# BUCK.net
KiCad netlist of a schematic drawn in Altium Designer
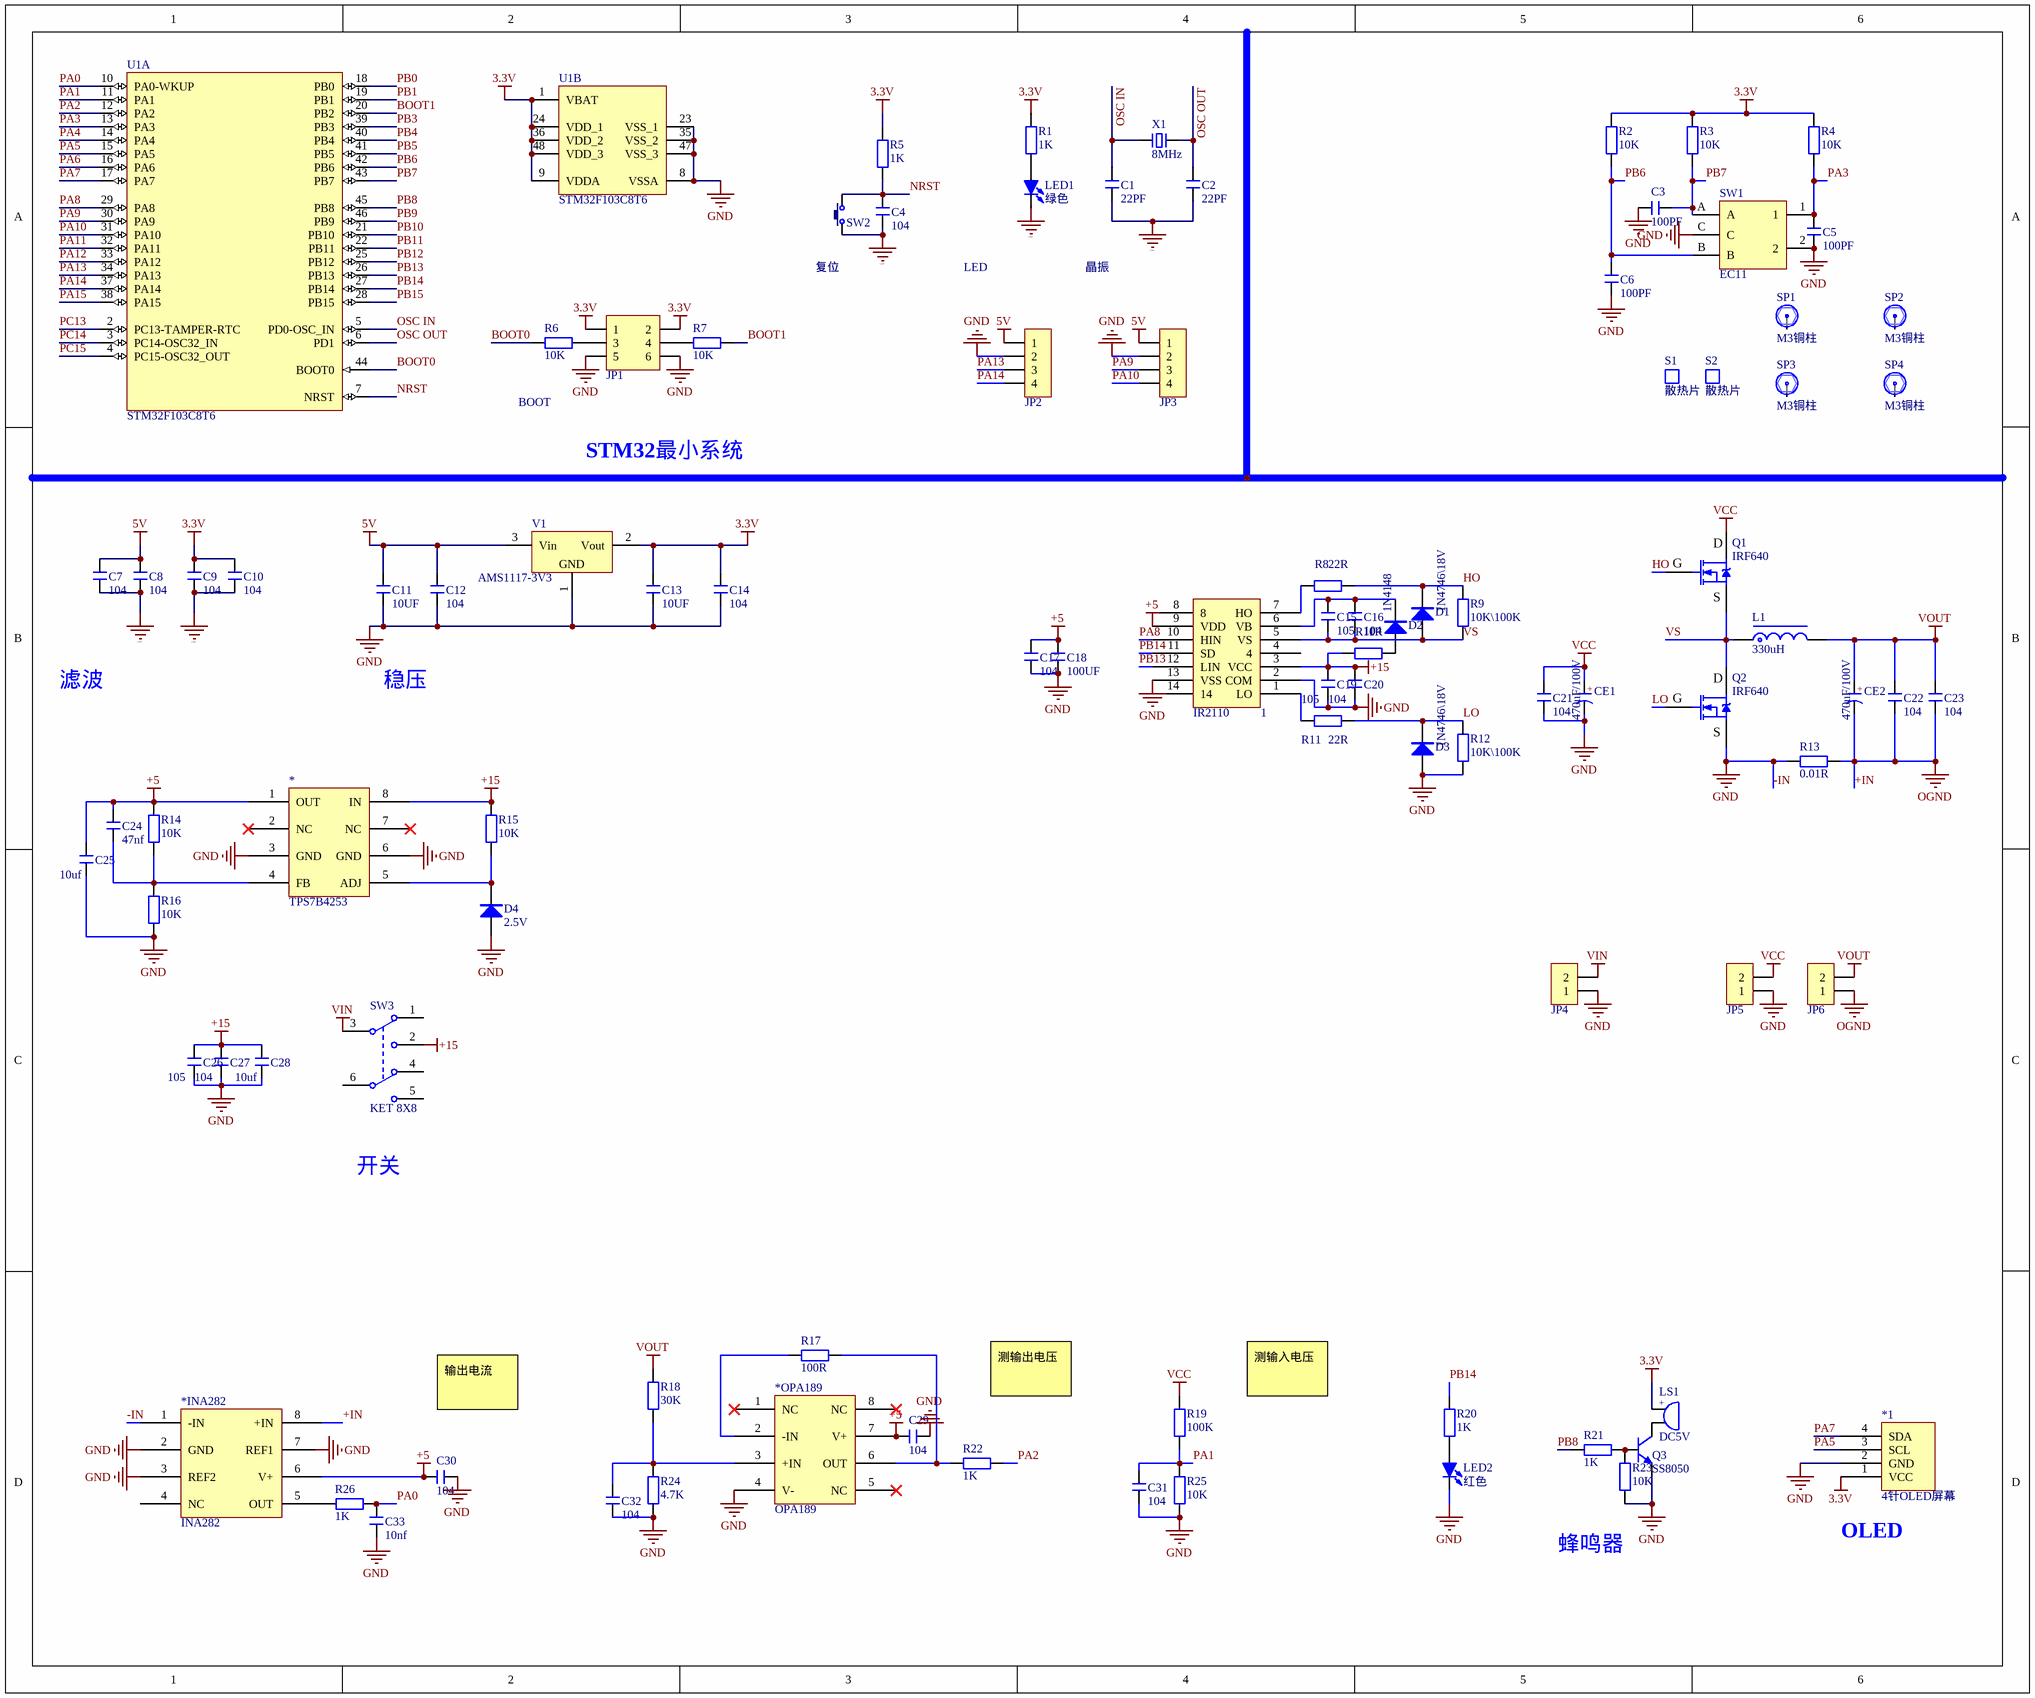
[diagram p0: BUCK开关电源.SchDoc]

(export (version "E")
  (design (tool "Eeschema 10.0.6"))
  (components
    (comp (ref "*")
      (value "TPS7B4253")
      (footprint "SOP8_M")
      (libsource (lib "1.1 - 电源类芯片") (part "TPS7B4253"))
    )
    (comp (ref "*1") (value "4针OLED屏幕") (footprint "4针OLED屏幕") (libsource (lib "4针OLED屏幕") (part "4针OLED屏幕")))
    (comp (ref "*INA282")
      (value "INA282")
      (footprint "SOP8_M")
      (libsource (lib "1.0 - 常见芯片") (part "INA282"))
    )
    (comp (ref "*OPA189")
      (value "OPA189")
      (footprint "SOP8_M")
      (libsource (lib "1.0 - 常见芯片") (part "OPA189"))
    )
    (comp (ref "1")
      (value "IR2110")
      (footprint "DIP14-300_MH")
      (libsource (lib "IR2110") (part "Component_1"))
    )
    (comp (ref "C1")
      (value "22PF")
      (footprint "C 0805_L")
      (description "贴片电容")
      (libsource (lib "0.1 - 电阻-电容-电感") (part "C"))
    )
    (comp (ref "C2")
      (value "22PF")
      (footprint "C 0805_L")
      (description "贴片电容")
      (libsource (lib "0.1 - 电阻-电容-电感") (part "C"))
    )
    (comp (ref "C3")
      (value "100PF")
      (footprint "C 0805_L")
      (description "贴片电容")
      (libsource (lib "0.1 - 电阻-电容-电感") (part "C"))
    )
    (comp (ref "C4")
      (value "104")
      (footprint "C 0805_L")
      (description "贴片电容")
      (libsource (lib "0.1 - 电阻-电容-电感") (part "C"))
    )
    (comp (ref "C5")
      (value "100PF")
      (footprint "C 0805_L")
      (description "贴片电容")
      (libsource (lib "0.1 - 电阻-电容-电感") (part "C"))
    )
    (comp (ref "C6")
      (value "100PF")
      (footprint "C 0805_L")
      (description "贴片电容")
      (libsource (lib "0.1 - 电阻-电容-电感") (part "C"))
    )
    (comp (ref "C7")
      (value "104")
      (footprint "C 0805_L")
      (description "贴片电容")
      (libsource (lib "0.1 - 电阻-电容-电感") (part "C"))
    )
    (comp (ref "C8")
      (value "104")
      (footprint "C 0805_L")
      (description "贴片电容")
      (libsource (lib "0.1 - 电阻-电容-电感") (part "C"))
    )
    (comp (ref "C9")
      (value "104")
      (footprint "C 0805_L")
      (description "贴片电容")
      (libsource (lib "0.1 - 电阻-电容-电感") (part "C"))
    )
    (comp (ref "C10")
      (value "104")
      (footprint "C 0805_L")
      (description "贴片电容")
      (libsource (lib "0.1 - 电阻-电容-电感") (part "C"))
    )
    (comp (ref "C11")
      (value "10UF")
      (footprint "C 0805_L")
      (description "贴片电容")
      (libsource (lib "0.1 - 电阻-电容-电感") (part "C"))
    )
    (comp (ref "C12")
      (value "104")
      (footprint "C 0805_L")
      (description "贴片电容")
      (libsource (lib "0.1 - 电阻-电容-电感") (part "C"))
    )
    (comp (ref "C13")
      (value "10UF")
      (footprint "C 0805_L")
      (description "贴片电容")
      (libsource (lib "0.1 - 电阻-电容-电感") (part "C"))
    )
    (comp (ref "C14")
      (value "104")
      (footprint "C 0805_L")
      (description "贴片电容")
      (libsource (lib "0.1 - 电阻-电容-电感") (part "C"))
    )
    (comp (ref "C15")
      (value "105")
      (footprint "C 0805_L")
      (description "贴片电容")
      (libsource (lib "0.1 - 电阻-电容-电感") (part "C"))
    )
    (comp (ref "C16")
      (value "104")
      (footprint "C 0805_L")
      (description "贴片电容")
      (libsource (lib "0.1 - 电阻-电容-电感") (part "C"))
    )
    (comp (ref "C17")
      (value "104")
      (footprint "C 0805_L")
      (description "贴片电容")
      (libsource (lib "0.1 - 电阻-电容-电感") (part "C"))
    )
    (comp (ref "C18")
      (value "100UF")
      (footprint "C 0805_L")
      (description "贴片电容")
      (libsource (lib "0.1 - 电阻-电容-电感") (part "C"))
    )
    (comp (ref "C19")
      (value "105")
      (footprint "C 0805_L")
      (description "贴片电容")
      (libsource (lib "0.1 - 电阻-电容-电感") (part "C"))
    )
    (comp (ref "C20")
      (value "104")
      (footprint "C 0805_L")
      (description "贴片电容")
      (libsource (lib "0.1 - 电阻-电容-电感") (part "C"))
    )
    (comp (ref "C21")
      (value "104")
      (footprint "C 0805_L")
      (description "贴片电容")
      (libsource (lib "0.1 - 电阻-电容-电感") (part "C"))
    )
    (comp (ref "C22")
      (value "104")
      (footprint "C 0805_L")
      (description "贴片电容")
      (libsource (lib "0.1 - 电阻-电容-电感") (part "C"))
    )
    (comp (ref "C23")
      (value "104")
      (footprint "C 0805_L")
      (description "贴片电容")
      (libsource (lib "0.1 - 电阻-电容-电感") (part "C"))
    )
    (comp (ref "C24")
      (value "47nf")
      (footprint "C 0805_L")
      (description "贴片电容")
      (libsource (lib "0.1 - 电阻-电容-电感") (part "C"))
    )
    (comp (ref "C25")
      (value "10uf")
      (footprint "C 0805_L")
      (description "贴片电容")
      (libsource (lib "0.1 - 电阻-电容-电感") (part "C"))
    )
    (comp (ref "C26")
      (value "105")
      (footprint "C 0805_L")
      (description "贴片电容")
      (libsource (lib "0.1 - 电阻-电容-电感") (part "C"))
    )
    (comp (ref "C27")
      (value "104")
      (footprint "C 0805_L")
      (description "贴片电容")
      (libsource (lib "0.1 - 电阻-电容-电感") (part "C"))
    )
    (comp (ref "C28")
      (value "10uf")
      (footprint "C 0805_L")
      (description "贴片电容")
      (libsource (lib "0.1 - 电阻-电容-电感") (part "C"))
    )
    (comp (ref "C29")
      (value "104")
      (footprint "C 0805_L")
      (description "贴片电容")
      (libsource (lib "0.1 - 电阻-电容-电感") (part "C"))
    )
    (comp (ref "C30")
      (value "104")
      (footprint "C 0805_L")
      (description "贴片电容")
      (libsource (lib "0.1 - 电阻-电容-电感") (part "C"))
    )
    (comp (ref "C31")
      (value "104")
      (footprint "C 0805_L")
      (description "贴片电容")
      (libsource (lib "0.1 - 电阻-电容-电感") (part "C"))
    )
    (comp (ref "C32")
      (value "104")
      (footprint "C 0805_L")
      (description "贴片电容")
      (libsource (lib "0.1 - 电阻-电容-电感") (part "C"))
    )
    (comp (ref "C33")
      (value "10nf")
      (footprint "C 0805_L")
      (description "贴片电容")
      (libsource (lib "0.1 - 电阻-电容-电感") (part "C"))
    )
    (comp (ref "CE1")
      (value "470uF/100V")
      (footprint "CAP 7.5*16*25 - BK")
      (description "直插电解电容")
      (libsource (lib "0.1 - 电阻-电容-电感") (part "CE"))
    )
    (comp (ref "CE2")
      (value "470uF/100V")
      (footprint "CAP 7.5*16*25 - BK")
      (description "直插电解电容")
      (libsource (lib "0.1 - 电阻-电容-电感") (part "CE"))
    )
    (comp (ref "D1")
      (value "1N474~{6}18V")
      (footprint "DO-35")
      (description "开关二极管")
      (libsource (lib "0.2 - 二极管-整流桥") (part "1N4148"))
    )
    (comp (ref "D2")
      (value "1N4148")
      (footprint "DO-35")
      (description "开关二极管")
      (libsource (lib "0.2 - 二极管-整流桥") (part "1N4148"))
    )
    (comp (ref "D3")
      (value "1N474~{6}18V")
      (footprint "DO-35")
      (description "开关二极管")
      (libsource (lib "0.2 - 二极管-整流桥") (part "1N4148"))
    )
    (comp (ref "D4")
      (value "2.5V")
      (footprint "DO-35")
      (description "开关二极管")
      (libsource (lib "0.2 - 二极管-整流桥") (part "1N4148"))
    )
    (comp (ref "JP1")
      (value "Header3X2")
      (footprint "HDR2.54-LI-2x3P")
      (description "3*2P接插件")
      (fields (field (name "版权归属") "封装库来自淘宝 ID：黄晶宝石"))
      (libsource (lib "5.4 - 接插件-脚距2.54 (100mil) ") (part "Header 3X2"))
    )
    (comp (ref "JP2")
      (value "HDR-1X4")
      (footprint "HDR2.54-WI-4P")
      (description "4P接插件")
      (fields (field (name "版权归属") "封装库来自淘宝 ID：黄晶宝石"))
      (libsource (lib "5.4 - 接插件-脚距2.54 (100mil) ") (part "Header 4"))
    )
    (comp (ref "JP3")
      (value "HDR-1X4")
      (footprint "HDR2.54-LI-4P")
      (description "4P接插件")
      (fields (field (name "版权归属") "封装库来自淘宝 ID：黄晶宝石"))
      (libsource (lib "5.4 - 接插件-脚距2.54 (100mil) ") (part "Header 4"))
    )
    (comp (ref "JP4")
      (value "HDR-1X2")
      (footprint "KF128-5.08-2P")
      (description "2P接插件")
      (fields (field (name "版权归属") "封装库来自淘宝卖家 ID：黄晶宝石"))
      (libsource (lib "6.1 - 接插件-脚距5.08 (200mil) ") (part "Header 2"))
    )
    (comp (ref "JP5")
      (value "HDR-1X2")
      (footprint "KF128-5.08-2P")
      (description "2P接插件")
      (fields (field (name "版权归属") "封装库来自淘宝卖家 ID：黄晶宝石"))
      (libsource (lib "6.1 - 接插件-脚距5.08 (200mil) ") (part "Header 2"))
    )
    (comp (ref "JP6")
      (value "HDR-1X2")
      (footprint "KF128-5.08-2P")
      (description "2P接插件")
      (fields (field (name "版权归属") "封装库来自淘宝卖家 ID：黄晶宝石"))
      (libsource (lib "6.1 - 接插件-脚距5.08 (200mil) ") (part "Header 2"))
    )
    (comp (ref "L1")
      (value "330uH")
      (footprint "直插磁环电感（大）")
      (description "功率磁环电感")
      (libsource (lib "0.1 - 电阻-电容-电感") (part "L-MR"))
    )
    (comp (ref "LED1")
      (value "绿色")
      (footprint "LED 0805W")
      (description "贴片LED")
      (fields (field (name "版权归属") "封装库来自淘宝 ID：黄晶宝石"))
      (libsource (lib "0.3 - LED发光二极管") (part "LED-SMD"))
    )
    (comp (ref "LED2")
      (value "红色")
      (footprint "LED 0603B")
      (description "贴片LED")
      (fields (field (name "版权归属") "封装库来自淘宝 ID：黄晶宝石"))
      (libsource (lib "0.3 - LED发光二极管") (part "LED-SMD"))
    )
    (comp (ref "LS1")
      (value "DC5V")
      (footprint "BEEP 7.6X12X7.5")
      (description "蜂鸣器")
      (fields (field (name "版权归属") "封装库来自淘宝 ID：黄晶宝石"))
      (libsource (lib "4.1 - 未分类器件") (part "BEEP"))
    )
    (comp (ref "Q1")
      (value "IRF640")
      (footprint "TO220A")
      (description "N沟场效应管")
      (libsource (lib "0.5 - 场效应管-可控硅") (part "IRF840"))
    )
    (comp (ref "Q2")
      (value "IRF640")
      (footprint "TO220A")
      (description "N沟场效应管")
      (libsource (lib "0.5 - 场效应管-可控硅") (part "IRF840"))
    )
    (comp (ref "Q3")
      (value "SS8050")
      (footprint "TO92A")
      (description "高频放大-NPN型")
      (fields (field (name "版权归属") "封装库来自淘宝 ID：黄晶宝石"))
      (libsource (lib "0.4 - 三极管") (part "8050-DIP"))
    )
    (comp (ref "R1")
      (value "1K")
      (footprint "R 0805_L")
      (description "贴片电阻")
      (fields (field (name "版权归属") "来自淘宝 ID：黄晶宝石"))
      (libsource (lib "0.1 - 电阻-电容-电感") (part "R"))
    )
    (comp (ref "R2")
      (value "10K")
      (footprint "R 0805_L")
      (description "贴片电阻")
      (fields (field (name "版权归属") "来自淘宝 ID：黄晶宝石"))
      (libsource (lib "0.1 - 电阻-电容-电感") (part "R"))
    )
    (comp (ref "R3")
      (value "10K")
      (footprint "R 0805_L")
      (description "贴片电阻")
      (fields (field (name "版权归属") "来自淘宝 ID：黄晶宝石"))
      (libsource (lib "0.1 - 电阻-电容-电感") (part "R"))
    )
    (comp (ref "R4")
      (value "10K")
      (footprint "R 0805_L")
      (description "贴片电阻")
      (fields (field (name "版权归属") "来自淘宝 ID：黄晶宝石"))
      (libsource (lib "0.1 - 电阻-电容-电感") (part "R"))
    )
    (comp (ref "R5")
      (value "1K")
      (footprint "R 0805_L")
      (description "贴片电阻")
      (fields (field (name "版权归属") "来自淘宝 ID：黄晶宝石"))
      (libsource (lib "0.1 - 电阻-电容-电感") (part "R"))
    )
    (comp (ref "R6")
      (value "10K")
      (footprint "R 0805_L")
      (description "贴片电阻")
      (fields (field (name "版权归属") "来自淘宝 ID：黄晶宝石"))
      (libsource (lib "0.1 - 电阻-电容-电感") (part "R"))
    )
    (comp (ref "R7")
      (value "10K")
      (footprint "R 0805_L")
      (description "贴片电阻")
      (fields (field (name "版权归属") "来自淘宝 ID：黄晶宝石"))
      (libsource (lib "0.1 - 电阻-电容-电感") (part "R"))
    )
    (comp (ref "R8")
      (value "22R")
      (footprint "R 0805_L")
      (description "贴片电阻")
      (fields (field (name "版权归属") "来自淘宝 ID：黄晶宝石"))
      (libsource (lib "0.1 - 电阻-电容-电感") (part "R"))
    )
    (comp (ref "R9")
      (value "10~{K}100K")
      (footprint "R 0805_L")
      (description "贴片电阻")
      (fields (field (name "版权归属") "来自淘宝 ID：黄晶宝石"))
      (libsource (lib "0.1 - 电阻-电容-电感") (part "R"))
    )
    (comp (ref "R10")
      (value "1R")
      (footprint "R 0805_L")
      (description "贴片电阻")
      (fields (field (name "版权归属") "来自淘宝 ID：黄晶宝石"))
      (libsource (lib "0.1 - 电阻-电容-电感") (part "R"))
    )
    (comp (ref "R11")
      (value "22R")
      (footprint "R 0805_L")
      (description "贴片电阻")
      (fields (field (name "版权归属") "来自淘宝 ID：黄晶宝石"))
      (libsource (lib "0.1 - 电阻-电容-电感") (part "R"))
    )
    (comp (ref "R12")
      (value "10~{K}100K")
      (footprint "R 0805_L")
      (description "贴片电阻")
      (fields (field (name "版权归属") "来自淘宝 ID：黄晶宝石"))
      (libsource (lib "0.1 - 电阻-电容-电感") (part "R"))
    )
    (comp (ref "R13")
      (value "0.01R")
      (footprint "R 2512_L")
      (description "贴片电阻")
      (fields (field (name "版权归属") "来自淘宝 ID：黄晶宝石"))
      (libsource (lib "0.1 - 电阻-电容-电感") (part "R"))
    )
    (comp (ref "R14")
      (value "10K")
      (footprint "R 0805_L")
      (description "贴片电阻")
      (fields (field (name "版权归属") "来自淘宝 ID：黄晶宝石"))
      (libsource (lib "0.1 - 电阻-电容-电感") (part "R"))
    )
    (comp (ref "R15")
      (value "10K")
      (footprint "R 0805_L")
      (description "贴片电阻")
      (fields (field (name "版权归属") "来自淘宝 ID：黄晶宝石"))
      (libsource (lib "0.1 - 电阻-电容-电感") (part "R"))
    )
    (comp (ref "R16")
      (value "10K")
      (footprint "R 0805_L")
      (description "贴片电阻")
      (fields (field (name "版权归属") "来自淘宝 ID：黄晶宝石"))
      (libsource (lib "0.1 - 电阻-电容-电感") (part "R"))
    )
    (comp (ref "R17")
      (value "100R")
      (footprint "R 0805_L")
      (description "贴片电阻")
      (fields (field (name "版权归属") "来自淘宝 ID：黄晶宝石"))
      (libsource (lib "0.1 - 电阻-电容-电感") (part "R"))
    )
    (comp (ref "R18")
      (value "30K")
      (footprint "R 0805_L")
      (description "贴片电阻")
      (fields (field (name "版权归属") "来自淘宝 ID：黄晶宝石"))
      (libsource (lib "0.1 - 电阻-电容-电感") (part "R"))
    )
    (comp (ref "R19")
      (value "100K")
      (footprint "R 0805_L")
      (description "贴片电阻")
      (fields (field (name "版权归属") "来自淘宝 ID：黄晶宝石"))
      (libsource (lib "0.1 - 电阻-电容-电感") (part "R"))
    )
    (comp (ref "R20")
      (value "1K")
      (footprint "R 0805_L")
      (description "贴片电阻")
      (fields (field (name "版权归属") "来自淘宝 ID：黄晶宝石"))
      (libsource (lib "0.1 - 电阻-电容-电感") (part "R"))
    )
    (comp (ref "R21")
      (value "1K")
      (footprint "R 0805_L")
      (description "贴片电阻")
      (fields (field (name "版权归属") "来自淘宝 ID：黄晶宝石"))
      (libsource (lib "0.1 - 电阻-电容-电感") (part "R"))
    )
    (comp (ref "R22")
      (value "1K")
      (footprint "R 0805_L")
      (description "贴片电阻")
      (fields (field (name "版权归属") "来自淘宝 ID：黄晶宝石"))
      (libsource (lib "0.1 - 电阻-电容-电感") (part "R"))
    )
    (comp (ref "R23")
      (value "10K")
      (footprint "R 0805_L")
      (description "贴片电阻")
      (fields (field (name "版权归属") "来自淘宝 ID：黄晶宝石"))
      (libsource (lib "0.1 - 电阻-电容-电感") (part "R"))
    )
    (comp (ref "R24")
      (value "4.7K")
      (footprint "R 0805_L")
      (description "贴片电阻")
      (fields (field (name "版权归属") "来自淘宝 ID：黄晶宝石"))
      (libsource (lib "0.1 - 电阻-电容-电感") (part "R"))
    )
    (comp (ref "R25")
      (value "10K")
      (footprint "R 0805_L")
      (description "贴片电阻")
      (fields (field (name "版权归属") "来自淘宝 ID：黄晶宝石"))
      (libsource (lib "0.1 - 电阻-电容-电感") (part "R"))
    )
    (comp (ref "R26")
      (value "1K")
      (footprint "R 0805_L")
      (description "贴片电阻")
      (fields (field (name "版权归属") "来自淘宝 ID：黄晶宝石"))
      (libsource (lib "0.1 - 电阻-电容-电感") (part "R"))
    )
    (comp (ref "S1")
      (value "散热片")
      (footprint "SRP10-15-21")
      (fields (field (name "版权归属") "封装库来自淘宝 ID：黄晶宝石"))
      (libsource (lib "4.1 - 未分类器件") (part "S1"))
    )
    (comp (ref "S2")
      (value "散热片")
      (footprint "SRP10-15-21")
      (fields (field (name "版权归属") "封装库来自淘宝 ID：黄晶宝石"))
      (libsource (lib "4.1 - 未分类器件") (part "S1"))
    )
    (comp (ref "SP1")
      (value "M3铜柱")
      (footprint "M3x4+6_L")
      (description "铜柱")
      (fields (field (name "版权归属") "封装库来自淘宝 ID：黄晶宝石"))
      (libsource (lib "4.1 - 未分类器件") (part "铜柱加头小焊盘"))
    )
    (comp (ref "SP2")
      (value "M3铜柱")
      (footprint "M3x4+6_L")
      (description "铜柱")
      (fields (field (name "版权归属") "封装库来自淘宝 ID：黄晶宝石"))
      (libsource (lib "4.1 - 未分类器件") (part "铜柱加头小焊盘"))
    )
    (comp (ref "SP3")
      (value "M3铜柱")
      (footprint "M3x4+6_L")
      (description "铜柱")
      (fields (field (name "版权归属") "封装库来自淘宝 ID：黄晶宝石"))
      (libsource (lib "4.1 - 未分类器件") (part "铜柱加头小焊盘"))
    )
    (comp (ref "SP4")
      (value "M3铜柱")
      (footprint "M3x4+6_L")
      (description "铜柱")
      (fields (field (name "版权归属") "封装库来自淘宝 ID：黄晶宝石"))
      (libsource (lib "4.1 - 未分类器件") (part "铜柱加头小焊盘"))
    )
    (comp (ref "SW1")
      (value "EC11")
      (footprint "EC11-B")
      (description "数字开关编码器")
      (fields (field (name "版权归属") "封装库来自淘宝 ID：黄晶宝石"))
      (libsource (lib "0.7 - 常用按键-开关") (part "EC11"))
    )
    (comp (ref "SW2")
      (value "3x6x5")
      (footprint "TSW SMD-3*6*2.5")
      (description "3x6轻触开关")
      (fields (field (name "版权归属") "封装库来自淘宝 ID：黄晶宝石"))
      (libsource (lib "0.7 - 常用按键-开关") (part "TSW 3x6"))
    )
    (comp (ref "SW3")
      (value "KET 8X8")
      (footprint "KFT DIP-8X8")
      (description "8*8自锁开关")
      (fields (field (name "版权归属") "封装库来自淘宝 ID：黄晶宝石"))
      (libsource (lib "0.7 - 常用按键-开关") (part "KET 8X8"))
    )
    (comp (ref "U1")
      (value "STM32F103C8T6")
      (footprint "LQFP48_N")
      (libsource (lib "2.3 - STM32 F1系列单片机") (part "STM32F103C8T6"))
    )
    (comp (ref "V1")
      (value "AMS1117-3V3")
      (footprint "SOT223_L")
      (description "三端稳压芯片")
      (libsource (lib "1.1 - 电源类芯片") (part "AMS1117"))
    )
    (comp (ref "X1")
      (value "8MHz")
      (footprint "OSC HC-49S")
      (description "2脚无源脚晶振")
      (fields (field (name "版权归属") "封装库来自淘宝卖家 ID：黄晶宝石"))
      (libsource (lib "2.0 - 保险丝-晶振-光耦") (part "XTAL-2P"))
    )
  )
  (nets
    (net (code "1") (name "+5") (class "Default")
      (node (ref "*") (pin "1") (pinfunction "OUT_1") (pintype "passive"))
      (node (ref "*INA282") (pin "6") (pinfunction "V+_6") (pintype "passive"))
      (node (ref "*OPA189") (pin "7") (pinfunction "V+_7") (pintype "passive"))
      (node (ref "1") (pin "9") (pinfunction "VDD_9") (pintype "passive"))
      (node (ref "C17") (pin "2") (pinfunction "2_2") (pintype "passive"))
      (node (ref "C18") (pin "2") (pinfunction "2_2") (pintype "passive"))
      (node (ref "C24") (pin "2") (pinfunction "2_2") (pintype "passive"))
      (node (ref "C25") (pin "2") (pinfunction "2_2") (pintype "passive"))
      (node (ref "C29") (pin "2") (pinfunction "2_2") (pintype "passive"))
      (node (ref "C30") (pin "1") (pinfunction "1_1") (pintype "passive"))
      (node (ref "R14") (pin "1") (pinfunction "1_1") (pintype "passive"))
    )
    (net (code "2") (name "+15") (class "Default")
      (node (ref "*") (pin "8") (pinfunction "IN_8") (pintype "passive"))
      (node (ref "1") (pin "3") (pinfunction "VCC_3") (pintype "passive"))
      (node (ref "C19") (pin "2") (pinfunction "2_2") (pintype "passive"))
      (node (ref "C20") (pin "2") (pinfunction "2_2") (pintype "passive"))
      (node (ref "C26") (pin "2") (pinfunction "2_2") (pintype "passive"))
      (node (ref "C27") (pin "2") (pinfunction "2_2") (pintype "passive"))
      (node (ref "C28") (pin "2") (pinfunction "2_2") (pintype "passive"))
      (node (ref "R10") (pin "1") (pinfunction "1_1") (pintype "passive"))
      (node (ref "R15") (pin "1") (pinfunction "1_1") (pintype "passive"))
      (node (ref "SW3") (pin "2") (pinfunction "COM2_2") (pintype "passive"))
    )
    (net (code "3") (name "/BOOT0") (class "Default")
      (node (ref "R6") (pin "1") (pinfunction "1_1") (pintype "passive"))
      (node (ref "U1") (pin "44") (pinfunction "BOOT0_44") (pintype "input"))
    )
    (net (code "4") (name "/BOOT1") (class "Default")
      (node (ref "R7") (pin "1") (pinfunction "1_1") (pintype "passive"))
      (node (ref "U1") (pin "20") (pinfunction "PB2_20") (pintype "bidirectional"))
    )
    (net (code "5") (name "/HO") (class "Default")
      (node (ref "D1") (pin "2") (pinfunction "K_2") (pintype "passive"))
      (node (ref "Q1") (pin "1") (pinfunction "G_1") (pintype "passive"))
      (node (ref "R8") (pin "2") (pinfunction "2_2") (pintype "passive"))
      (node (ref "R9") (pin "2") (pinfunction "2_2") (pintype "passive"))
    )
    (net (code "6") (name "/LO") (class "Default")
      (node (ref "D3") (pin "2") (pinfunction "K_2") (pintype "passive"))
      (node (ref "Q2") (pin "1") (pinfunction "G_1") (pintype "passive"))
      (node (ref "R11") (pin "2") (pinfunction "2_2") (pintype "passive"))
      (node (ref "R12") (pin "2") (pinfunction "2_2") (pintype "passive"))
    )
    (net (code "7") (name "/NRST") (class "Default")
      (node (ref "C4") (pin "1") (pinfunction "1_1") (pintype "passive"))
      (node (ref "R5") (pin "1") (pinfunction "1_1") (pintype "passive"))
      (node (ref "SW2") (pin "2") (pinfunction "2_2") (pintype "passive"))
      (node (ref "U1") (pin "7") (pinfunction "NRST_7") (pintype "bidirectional"))
    )
    (net (code "8") (name "/OSC IN") (class "Default")
      (node (ref "C1") (pin "1") (pinfunction "1_1") (pintype "passive"))
      (node (ref "U1") (pin "5") (pinfunction "PD0-OSC_IN_5") (pintype "bidirectional"))
      (node (ref "X1") (pin "1") (pinfunction "1_1") (pintype "passive"))
    )
    (net (code "9") (name "/OSC OUT") (class "Default")
      (node (ref "C2") (pin "1") (pinfunction "1_1") (pintype "passive"))
      (node (ref "U1") (pin "6") (pinfunction "PD1_6") (pintype "bidirectional"))
      (node (ref "X1") (pin "2") (pinfunction "2_2") (pintype "passive"))
    )
    (net (code "10") (name "/PA0") (class "Default")
      (node (ref "C33") (pin "2") (pinfunction "2_2") (pintype "passive"))
      (node (ref "R26") (pin "1") (pinfunction "1_1") (pintype "passive"))
      (node (ref "U1") (pin "10") (pinfunction "PA0-WKUP_10") (pintype "bidirectional"))
    )
    (net (code "11") (name "/PA1") (class "Default")
      (node (ref "C31") (pin "2") (pinfunction "2_2") (pintype "passive"))
      (node (ref "R19") (pin "2") (pinfunction "2_2") (pintype "passive"))
      (node (ref "R25") (pin "1") (pinfunction "1_1") (pintype "passive"))
      (node (ref "U1") (pin "11") (pinfunction "PA1_11") (pintype "bidirectional"))
    )
    (net (code "12") (name "/PA2") (class "Default")
      (node (ref "R22") (pin "1") (pinfunction "1_1") (pintype "passive"))
      (node (ref "U1") (pin "12") (pinfunction "PA2_12") (pintype "bidirectional"))
    )
    (net (code "13") (name "/PA3") (class "Default")
      (node (ref "C5") (pin "1") (pinfunction "1_1") (pintype "passive"))
      (node (ref "R4") (pin "1") (pinfunction "1_1") (pintype "passive"))
      (node (ref "SW1") (pin "1") (pinfunction "1_1") (pintype "passive"))
      (node (ref "U1") (pin "13") (pinfunction "PA3_13") (pintype "bidirectional"))
    )
    (net (code "14") (name "/PA4") (class "Default")
      (node (ref "U1") (pin "14") (pinfunction "PA4_14") (pintype "bidirectional"))
    )
    (net (code "15") (name "/PA5") (class "Default")
      (node (ref "*1") (pin "3") (pinfunction "SCL_3") (pintype "passive"))
      (node (ref "U1") (pin "15") (pinfunction "PA5_15") (pintype "bidirectional"))
    )
    (net (code "16") (name "/PA6") (class "Default")
      (node (ref "U1") (pin "16") (pinfunction "PA6_16") (pintype "bidirectional"))
    )
    (net (code "17") (name "/PA7") (class "Default")
      (node (ref "*1") (pin "4") (pinfunction "SDA_4") (pintype "passive"))
      (node (ref "U1") (pin "17") (pinfunction "PA7_17") (pintype "bidirectional"))
    )
    (net (code "18") (name "/PA8") (class "Default")
      (node (ref "1") (pin "10") (pinfunction "HIN_10") (pintype "passive"))
      (node (ref "U1") (pin "29") (pinfunction "PA8_29") (pintype "bidirectional"))
    )
    (net (code "19") (name "/PA9") (class "Default")
      (node (ref "JP3") (pin "3") (pinfunction "3_3") (pintype "passive"))
      (node (ref "U1") (pin "30") (pinfunction "PA9_30") (pintype "bidirectional"))
    )
    (net (code "20") (name "/PA10") (class "Default")
      (node (ref "JP3") (pin "4") (pinfunction "4_4") (pintype "passive"))
      (node (ref "U1") (pin "31") (pinfunction "PA10_31") (pintype "bidirectional"))
    )
    (net (code "21") (name "/PA11") (class "Default")
      (node (ref "U1") (pin "32") (pinfunction "PA11_32") (pintype "bidirectional"))
    )
    (net (code "22") (name "/PA12") (class "Default")
      (node (ref "U1") (pin "33") (pinfunction "PA12_33") (pintype "bidirectional"))
    )
    (net (code "23") (name "/PA13") (class "Default")
      (node (ref "JP2") (pin "3") (pinfunction "3_3") (pintype "passive"))
      (node (ref "U1") (pin "34") (pinfunction "PA13_34") (pintype "bidirectional"))
    )
    (net (code "24") (name "/PA14") (class "Default")
      (node (ref "JP2") (pin "4") (pinfunction "4_4") (pintype "passive"))
      (node (ref "U1") (pin "37") (pinfunction "PA14_37") (pintype "bidirectional"))
    )
    (net (code "25") (name "/PA15") (class "Default")
      (node (ref "U1") (pin "38") (pinfunction "PA15_38") (pintype "bidirectional"))
    )
    (net (code "26") (name "/PB0") (class "Default")
      (node (ref "U1") (pin "18") (pinfunction "PB0_18") (pintype "bidirectional"))
    )
    (net (code "27") (name "/PB1") (class "Default")
      (node (ref "U1") (pin "19") (pinfunction "PB1_19") (pintype "bidirectional"))
    )
    (net (code "28") (name "/PB3") (class "Default")
      (node (ref "U1") (pin "39") (pinfunction "PB3_39") (pintype "bidirectional"))
    )
    (net (code "29") (name "/PB4") (class "Default")
      (node (ref "U1") (pin "40") (pinfunction "PB4_40") (pintype "bidirectional"))
    )
    (net (code "30") (name "/PB5") (class "Default")
      (node (ref "U1") (pin "41") (pinfunction "PB5_41") (pintype "bidirectional"))
    )
    (net (code "31") (name "/PB6") (class "Default")
      (node (ref "C6") (pin "2") (pinfunction "2_2") (pintype "passive"))
      (node (ref "R2") (pin "1") (pinfunction "1_1") (pintype "passive"))
      (node (ref "SW1") (pin "B") (pinfunction "B_B") (pintype "passive"))
      (node (ref "U1") (pin "42") (pinfunction "PB6_42") (pintype "bidirectional"))
    )
    (net (code "32") (name "/PB7") (class "Default")
      (node (ref "C3") (pin "1") (pinfunction "1_1") (pintype "passive"))
      (node (ref "R3") (pin "1") (pinfunction "1_1") (pintype "passive"))
      (node (ref "SW1") (pin "A") (pinfunction "A_A") (pintype "passive"))
      (node (ref "U1") (pin "43") (pinfunction "PB7_43") (pintype "bidirectional"))
    )
    (net (code "33") (name "/PB8") (class "Default")
      (node (ref "R21") (pin "2") (pinfunction "2_2") (pintype "passive"))
      (node (ref "U1") (pin "45") (pinfunction "PB8_45") (pintype "bidirectional"))
    )
    (net (code "34") (name "/PB9") (class "Default")
      (node (ref "U1") (pin "46") (pinfunction "PB9_46") (pintype "bidirectional"))
    )
    (net (code "35") (name "/PB10") (class "Default")
      (node (ref "U1") (pin "21") (pinfunction "PB10_21") (pintype "bidirectional"))
    )
    (net (code "36") (name "/PB11") (class "Default")
      (node (ref "U1") (pin "22") (pinfunction "PB11_22") (pintype "bidirectional"))
    )
    (net (code "37") (name "/PB12") (class "Default")
      (node (ref "U1") (pin "25") (pinfunction "PB12_25") (pintype "bidirectional"))
    )
    (net (code "38") (name "/PB13") (class "Default")
      (node (ref "1") (pin "12") (pinfunction "LIN_12") (pintype "passive"))
      (node (ref "U1") (pin "26") (pinfunction "PB13_26") (pintype "bidirectional"))
    )
    (net (code "39") (name "/PB14") (class "Default")
      (node (ref "1") (pin "11") (pinfunction "SD_11") (pintype "passive"))
      (node (ref "R20") (pin "2") (pinfunction "2_2") (pintype "passive"))
      (node (ref "U1") (pin "27") (pinfunction "PB14_27") (pintype "bidirectional"))
    )
    (net (code "40") (name "/PB15") (class "Default")
      (node (ref "U1") (pin "28") (pinfunction "PB15_28") (pintype "bidirectional"))
    )
    (net (code "41") (name "/PC13") (class "Default")
      (node (ref "U1") (pin "2") (pinfunction "PC13-TAMPER-RTC_2") (pintype "bidirectional"))
    )
    (net (code "42") (name "/PC14") (class "Default")
      (node (ref "U1") (pin "3") (pinfunction "PC14-OSC32_IN_3") (pintype "bidirectional"))
    )
    (net (code "43") (name "/PC15") (class "Default")
      (node (ref "U1") (pin "4") (pinfunction "PC15-OSC32_OUT_4") (pintype "bidirectional"))
    )
    (net (code "44") (name "/VS") (class "Default")
      (node (ref "1") (pin "5") (pinfunction "VS_5") (pintype "passive"))
      (node (ref "C15") (pin "1") (pinfunction "1_1") (pintype "passive"))
      (node (ref "C16") (pin "1") (pinfunction "1_1") (pintype "passive"))
      (node (ref "D1") (pin "1") (pinfunction "A_1") (pintype "passive"))
      (node (ref "L1") (pin "1") (pinfunction "1_1") (pintype "passive"))
      (node (ref "Q1") (pin "3") (pinfunction "S_3") (pintype "passive"))
      (node (ref "Q2") (pin "2") (pinfunction "D_2") (pintype "passive"))
      (node (ref "R9") (pin "1") (pinfunction "1_1") (pintype "passive"))
    )
    (net (code "45") (name "3.3V") (class "Default")
      (node (ref "*1") (pin "1") (pinfunction "VCC_1") (pintype "passive"))
      (node (ref "C10") (pin "2") (pinfunction "2_2") (pintype "passive"))
      (node (ref "C13") (pin "2") (pinfunction "2_2") (pintype "passive"))
      (node (ref "C14") (pin "2") (pinfunction "2_2") (pintype "passive"))
      (node (ref "C9") (pin "2") (pinfunction "2_2") (pintype "passive"))
      (node (ref "JP1") (pin "1") (pinfunction "1_1") (pintype "passive"))
      (node (ref "JP1") (pin "2") (pinfunction "2_2") (pintype "passive"))
      (node (ref "LS1") (pin "1") (pinfunction "1_1") (pintype "passive"))
      (node (ref "R1") (pin "2") (pinfunction "2_2") (pintype "passive"))
      (node (ref "R2") (pin "2") (pinfunction "2_2") (pintype "passive"))
      (node (ref "R3") (pin "2") (pinfunction "2_2") (pintype "passive"))
      (node (ref "R4") (pin "2") (pinfunction "2_2") (pintype "passive"))
      (node (ref "R5") (pin "2") (pinfunction "2_2") (pintype "passive"))
      (node (ref "U1") (pin "1") (pinfunction "VBAT_1") (pintype "power_in"))
      (node (ref "U1") (pin "24") (pinfunction "VDD_1_24") (pintype "power_in"))
      (node (ref "U1") (pin "36") (pinfunction "VDD_2_36") (pintype "power_in"))
      (node (ref "U1") (pin "48") (pinfunction "VDD_3_48") (pintype "power_in"))
      (node (ref "U1") (pin "9") (pinfunction "VDDA_9") (pintype "power_in"))
      (node (ref "V1") (pin "2") (pinfunction "Vout_2") (pintype "passive"))
    )
    (net (code "46") (name "5V") (class "Default")
      (node (ref "C11") (pin "2") (pinfunction "2_2") (pintype "passive"))
      (node (ref "C12") (pin "2") (pinfunction "2_2") (pintype "passive"))
      (node (ref "C7") (pin "2") (pinfunction "2_2") (pintype "passive"))
      (node (ref "C8") (pin "2") (pinfunction "2_2") (pintype "passive"))
      (node (ref "JP2") (pin "1") (pinfunction "1_1") (pintype "passive"))
      (node (ref "JP3") (pin "1") (pinfunction "1_1") (pintype "passive"))
      (node (ref "V1") (pin "3") (pinfunction "Vin_3") (pintype "passive"))
    )
    (net (code "47") (name "GND") (class "Default")
      (node (ref "*") (pin "3") (pinfunction "GND_3") (pintype "passive"))
      (node (ref "*") (pin "6") (pinfunction "GND_6") (pintype "passive"))
      (node (ref "*1") (pin "2") (pinfunction "GND_2") (pintype "passive"))
      (node (ref "*INA282") (pin "1") (pinfunction "-IN_1") (pintype "passive"))
      (node (ref "*INA282") (pin "2") (pinfunction "GND_2") (pintype "passive"))
      (node (ref "*INA282") (pin "3") (pinfunction "REF2_3") (pintype "passive"))
      (node (ref "*OPA189") (pin "4") (pinfunction "V-_4") (pintype "passive"))
      (node (ref "1") (pin "13") (pinfunction "VSS_13") (pintype "passive"))
      (node (ref "1") (pin "2") (pinfunction "COM_2") (pintype "passive"))
      (node (ref "C1") (pin "2") (pinfunction "2_2") (pintype "passive"))
      (node (ref "C10") (pin "1") (pinfunction "1_1") (pintype "passive"))
      (node (ref "C11") (pin "1") (pinfunction "1_1") (pintype "passive"))
      (node (ref "C12") (pin "1") (pinfunction "1_1") (pintype "passive"))
      (node (ref "C13") (pin "1") (pinfunction "1_1") (pintype "passive"))
      (node (ref "C14") (pin "1") (pinfunction "1_1") (pintype "passive"))
      (node (ref "C17") (pin "1") (pinfunction "1_1") (pintype "passive"))
      (node (ref "C18") (pin "1") (pinfunction "1_1") (pintype "passive"))
      (node (ref "C19") (pin "1") (pinfunction "1_1") (pintype "passive"))
      (node (ref "C2") (pin "2") (pinfunction "2_2") (pintype "passive"))
      (node (ref "C20") (pin "1") (pinfunction "1_1") (pintype "passive"))
      (node (ref "C21") (pin "1") (pinfunction "1_1") (pintype "passive"))
      (node (ref "C25") (pin "1") (pinfunction "1_1") (pintype "passive"))
      (node (ref "C26") (pin "1") (pinfunction "1_1") (pintype "passive"))
      (node (ref "C27") (pin "1") (pinfunction "1_1") (pintype "passive"))
      (node (ref "C28") (pin "1") (pinfunction "1_1") (pintype "passive"))
      (node (ref "C29") (pin "1") (pinfunction "1_1") (pintype "passive"))
      (node (ref "C3") (pin "2") (pinfunction "2_2") (pintype "passive"))
      (node (ref "C30") (pin "2") (pinfunction "2_2") (pintype "passive"))
      (node (ref "C31") (pin "1") (pinfunction "1_1") (pintype "passive"))
      (node (ref "C32") (pin "1") (pinfunction "1_1") (pintype "passive"))
      (node (ref "C33") (pin "1") (pinfunction "1_1") (pintype "passive"))
      (node (ref "C4") (pin "2") (pinfunction "2_2") (pintype "passive"))
      (node (ref "C5") (pin "2") (pinfunction "2_2") (pintype "passive"))
      (node (ref "C6") (pin "1") (pinfunction "1_1") (pintype "passive"))
      (node (ref "C7") (pin "1") (pinfunction "1_1") (pintype "passive"))
      (node (ref "C8") (pin "1") (pinfunction "1_1") (pintype "passive"))
      (node (ref "C9") (pin "1") (pinfunction "1_1") (pintype "passive"))
      (node (ref "CE1") (pin "2") (pinfunction "K_2") (pintype "passive"))
      (node (ref "D3") (pin "1") (pinfunction "A_1") (pintype "passive"))
      (node (ref "D4") (pin "1") (pinfunction "A_1") (pintype "passive"))
      (node (ref "JP1") (pin "5") (pinfunction "5_5") (pintype "passive"))
      (node (ref "JP1") (pin "6") (pinfunction "6_6") (pintype "passive"))
      (node (ref "JP2") (pin "2") (pinfunction "2_2") (pintype "passive"))
      (node (ref "JP3") (pin "2") (pinfunction "2_2") (pintype "passive"))
      (node (ref "JP4") (pin "1") (pinfunction "1_1") (pintype "passive"))
      (node (ref "JP5") (pin "1") (pinfunction "1_1") (pintype "passive"))
      (node (ref "LED1") (pin "2") (pinfunction "K_2") (pintype "passive"))
      (node (ref "LED2") (pin "2") (pinfunction "K_2") (pintype "passive"))
      (node (ref "Q2") (pin "3") (pinfunction "S_3") (pintype "passive"))
      (node (ref "Q3") (pin "1") (pinfunction "E_1") (pintype "passive"))
      (node (ref "R12") (pin "1") (pinfunction "1_1") (pintype "passive"))
      (node (ref "R13") (pin "1") (pinfunction "1_1") (pintype "passive"))
      (node (ref "R16") (pin "2") (pinfunction "2_2") (pintype "passive"))
      (node (ref "R23") (pin "1") (pinfunction "1_1") (pintype "passive"))
      (node (ref "R24") (pin "2") (pinfunction "2_2") (pintype "passive"))
      (node (ref "R25") (pin "2") (pinfunction "2_2") (pintype "passive"))
      (node (ref "SW1") (pin "2") (pinfunction "2_2") (pintype "passive"))
      (node (ref "SW1") (pin "C") (pinfunction "C_C") (pintype "passive"))
      (node (ref "SW2") (pin "1") (pinfunction "1_1") (pintype "passive"))
      (node (ref "U1") (pin "23") (pinfunction "VSS_1_23") (pintype "power_in"))
      (node (ref "U1") (pin "35") (pinfunction "VSS_2_35") (pintype "power_in"))
      (node (ref "U1") (pin "47") (pinfunction "VSS_3_47") (pintype "power_in"))
      (node (ref "U1") (pin "8") (pinfunction "VSSA_8") (pintype "power_in"))
      (node (ref "V1") (pin "1") (pinfunction "GND_1") (pintype "passive"))
    )
    (net (code "48") (name "Net-(*-ADJ)") (class "Default")
      (node (ref "*") (pin "5") (pinfunction "ADJ_5") (pintype "passive"))
      (node (ref "D4") (pin "2") (pinfunction "K_2") (pintype "passive"))
      (node (ref "R15") (pin "2") (pinfunction "2_2") (pintype "passive"))
    )
    (net (code "49") (name "Net-(*-FB)") (class "Default")
      (node (ref "*") (pin "4") (pinfunction "FB_4") (pintype "passive"))
      (node (ref "C24") (pin "1") (pinfunction "1_1") (pintype "passive"))
      (node (ref "R14") (pin "2") (pinfunction "2_2") (pintype "passive"))
      (node (ref "R16") (pin "1") (pinfunction "1_1") (pintype "passive"))
    )
    (net (code "50") (name "Net-(*INA282-OUT)") (class "Default")
      (node (ref "*INA282") (pin "5") (pinfunction "OUT_5") (pintype "passive"))
      (node (ref "R26") (pin "2") (pinfunction "2_2") (pintype "passive"))
    )
    (net (code "51") (name "Net-(*OPA189-+IN)") (class "Default")
      (node (ref "*OPA189") (pin "3") (pinfunction "+IN_3") (pintype "passive"))
      (node (ref "C32") (pin "2") (pinfunction "2_2") (pintype "passive"))
      (node (ref "R18") (pin "2") (pinfunction "2_2") (pintype "passive"))
      (node (ref "R24") (pin "1") (pinfunction "1_1") (pintype "passive"))
    )
    (net (code "52") (name "Net-(*OPA189--IN)") (class "Default")
      (node (ref "*OPA189") (pin "2") (pinfunction "-IN_2") (pintype "passive"))
      (node (ref "R17") (pin "2") (pinfunction "2_2") (pintype "passive"))
    )
    (net (code "53") (name "Net-(*OPA189-OUT)") (class "Default")
      (node (ref "*OPA189") (pin "6") (pinfunction "OUT_6") (pintype "passive"))
      (node (ref "R17") (pin "1") (pinfunction "1_1") (pintype "passive"))
      (node (ref "R22") (pin "2") (pinfunction "2_2") (pintype "passive"))
    )
    (net (code "54") (name "Net-(1-HO)") (class "Default")
      (node (ref "1") (pin "7") (pinfunction "HO_7") (pintype "passive"))
      (node (ref "R8") (pin "1") (pinfunction "1_1") (pintype "passive"))
    )
    (net (code "55") (name "Net-(1-LO)") (class "Default")
      (node (ref "1") (pin "1") (pinfunction "LO_1") (pintype "passive"))
      (node (ref "R11") (pin "1") (pinfunction "1_1") (pintype "passive"))
    )
    (net (code "56") (name "Net-(1-VB)") (class "Default")
      (node (ref "1") (pin "6") (pinfunction "VB_6") (pintype "passive"))
      (node (ref "C15") (pin "2") (pinfunction "2_2") (pintype "passive"))
      (node (ref "C16") (pin "2") (pinfunction "2_2") (pintype "passive"))
      (node (ref "D2") (pin "2") (pinfunction "K_2") (pintype "passive"))
    )
    (net (code "57") (name "Net-(D2-A)") (class "Default")
      (node (ref "D2") (pin "1") (pinfunction "A_1") (pintype "passive"))
      (node (ref "R10") (pin "2") (pinfunction "2_2") (pintype "passive"))
    )
    (net (code "58") (name "Net-(JP1-Pad3)") (class "Default")
      (node (ref "JP1") (pin "3") (pinfunction "3_3") (pintype "passive"))
      (node (ref "R6") (pin "2") (pinfunction "2_2") (pintype "passive"))
    )
    (net (code "59") (name "Net-(JP1-Pad4)") (class "Default")
      (node (ref "JP1") (pin "4") (pinfunction "4_4") (pintype "passive"))
      (node (ref "R7") (pin "2") (pinfunction "2_2") (pintype "passive"))
    )
    (net (code "60") (name "Net-(LED1-A)") (class "Default")
      (node (ref "LED1") (pin "1") (pinfunction "A_1") (pintype "passive"))
      (node (ref "R1") (pin "1") (pinfunction "1_1") (pintype "passive"))
    )
    (net (code "61") (name "Net-(LED2-A)") (class "Default")
      (node (ref "LED2") (pin "1") (pinfunction "A_1") (pintype "passive"))
      (node (ref "R20") (pin "1") (pinfunction "1_1") (pintype "passive"))
    )
    (net (code "62") (name "Net-(Q3-B)") (class "Default")
      (node (ref "Q3") (pin "2") (pinfunction "B_2") (pintype "passive"))
      (node (ref "R21") (pin "1") (pinfunction "1_1") (pintype "passive"))
      (node (ref "R23") (pin "2") (pinfunction "2_2") (pintype "passive"))
    )
    (net (code "63") (name "Net-(Q3-C)") (class "Default")
      (node (ref "LS1") (pin "2") (pinfunction "2_2") (pintype "passive"))
      (node (ref "Q3") (pin "3") (pinfunction "C_3") (pintype "passive"))
    )
    (net (code "64") (name "OGND") (class "Default")
      (node (ref "*INA282") (pin "8") (pinfunction "+IN_8") (pintype "passive"))
      (node (ref "C22") (pin "1") (pinfunction "1_1") (pintype "passive"))
      (node (ref "C23") (pin "1") (pinfunction "1_1") (pintype "passive"))
      (node (ref "CE2") (pin "2") (pinfunction "K_2") (pintype "passive"))
      (node (ref "JP6") (pin "1") (pinfunction "1_1") (pintype "passive"))
      (node (ref "R13") (pin "2") (pinfunction "2_2") (pintype "passive"))
    )
    (net (code "65") (name "VCC") (class "Default")
      (node (ref "C21") (pin "2") (pinfunction "2_2") (pintype "passive"))
      (node (ref "CE1") (pin "1") (pinfunction "A_1") (pintype "passive"))
      (node (ref "JP5") (pin "2") (pinfunction "2_2") (pintype "passive"))
      (node (ref "Q1") (pin "2") (pinfunction "D_2") (pintype "passive"))
      (node (ref "R19") (pin "1") (pinfunction "1_1") (pintype "passive"))
    )
    (net (code "66") (name "VIN") (class "Default")
      (node (ref "JP4") (pin "2") (pinfunction "2_2") (pintype "passive"))
      (node (ref "SW3") (pin "3") (pinfunction "NO1_3") (pintype "passive"))
    )
    (net (code "67") (name "VOUT") (class "Default")
      (node (ref "C22") (pin "2") (pinfunction "2_2") (pintype "passive"))
      (node (ref "C23") (pin "2") (pinfunction "2_2") (pintype "passive"))
      (node (ref "CE2") (pin "1") (pinfunction "A_1") (pintype "passive"))
      (node (ref "JP6") (pin "2") (pinfunction "2_2") (pintype "passive"))
      (node (ref "L1") (pin "2") (pinfunction "2_2") (pintype "passive"))
      (node (ref "R18") (pin "1") (pinfunction "1_1") (pintype "passive"))
    )
    (net (code "68") (name "unconnected-(*-NC-Pad2)") (class "Default")
      (node (ref "*") (pin "2") (pinfunction "NC_2") (pintype "passive+no_connect"))
    )
    (net (code "69") (name "unconnected-(*-NC-Pad7)") (class "Default")
      (node (ref "*") (pin "7") (pinfunction "NC_7") (pintype "passive+no_connect"))
    )
    (net (code "70") (name "unconnected-(*INA282-NC-Pad4)") (class "Default")
      (node (ref "*INA282") (pin "4") (pinfunction "NC_4") (pintype "passive"))
    )
    (net (code "71") (name "unconnected-(*INA282-REF1-Pad7)") (class "Default")
      (node (ref "*INA282") (pin "7") (pinfunction "REF1_7") (pintype "passive"))
    )
    (net (code "72") (name "unconnected-(*OPA189-NC-Pad1)") (class "Default")
      (node (ref "*OPA189") (pin "1") (pinfunction "NC_1") (pintype "passive+no_connect"))
    )
    (net (code "73") (name "unconnected-(*OPA189-NC-Pad5)") (class "Default")
      (node (ref "*OPA189") (pin "5") (pinfunction "NC_5") (pintype "passive+no_connect"))
    )
    (net (code "74") (name "unconnected-(*OPA189-NC-Pad8)") (class "Default")
      (node (ref "*OPA189") (pin "8") (pinfunction "NC_8") (pintype "passive+no_connect"))
    )
    (net (code "75") (name "unconnected-(1-Pad4)") (class "Default")
      (node (ref "1") (pin "4") (pinfunction "4_4") (pintype "passive"))
    )
    (net (code "76") (name "unconnected-(1-Pad8)") (class "Default")
      (node (ref "1") (pin "8") (pinfunction "8_8") (pintype "passive"))
    )
    (net (code "77") (name "unconnected-(1-Pad14)") (class "Default")
      (node (ref "1") (pin "14") (pinfunction "14_14") (pintype "passive"))
    )
    (net (code "78") (name "unconnected-(SP1-Pad1)") (class "Default")
      (node (ref "SP1") (pin "1") (pinfunction "1_1") (pintype "passive"))
    )
    (net (code "79") (name "unconnected-(SP2-Pad1)") (class "Default")
      (node (ref "SP2") (pin "1") (pinfunction "1_1") (pintype "passive"))
    )
    (net (code "80") (name "unconnected-(SP3-Pad1)") (class "Default")
      (node (ref "SP3") (pin "1") (pinfunction "1_1") (pintype "passive"))
    )
    (net (code "81") (name "unconnected-(SP4-Pad1)") (class "Default")
      (node (ref "SP4") (pin "1") (pinfunction "1_1") (pintype "passive"))
    )
    (net (code "82") (name "unconnected-(SW3-COM2-Pad5)") (class "Default")
      (node (ref "SW3") (pin "5") (pinfunction "COM2_5") (pintype "passive"))
    )
    (net (code "83") (name "unconnected-(SW3-NC1-Pad1)") (class "Default")
      (node (ref "SW3") (pin "1") (pinfunction "NC1_1") (pintype "passive"))
    )
    (net (code "84") (name "unconnected-(SW3-NC2-Pad6)") (class "Default")
      (node (ref "SW3") (pin "6") (pinfunction "NC2_6") (pintype "passive"))
    )
    (net (code "85") (name "unconnected-(SW3-NO2-Pad4)") (class "Default")
      (node (ref "SW3") (pin "4") (pinfunction "NO2_4") (pintype "passive"))
    )
  )
)
